# Flahser_4CH_555.net
KiCad netlist of a schematic drawn in Altium Designer
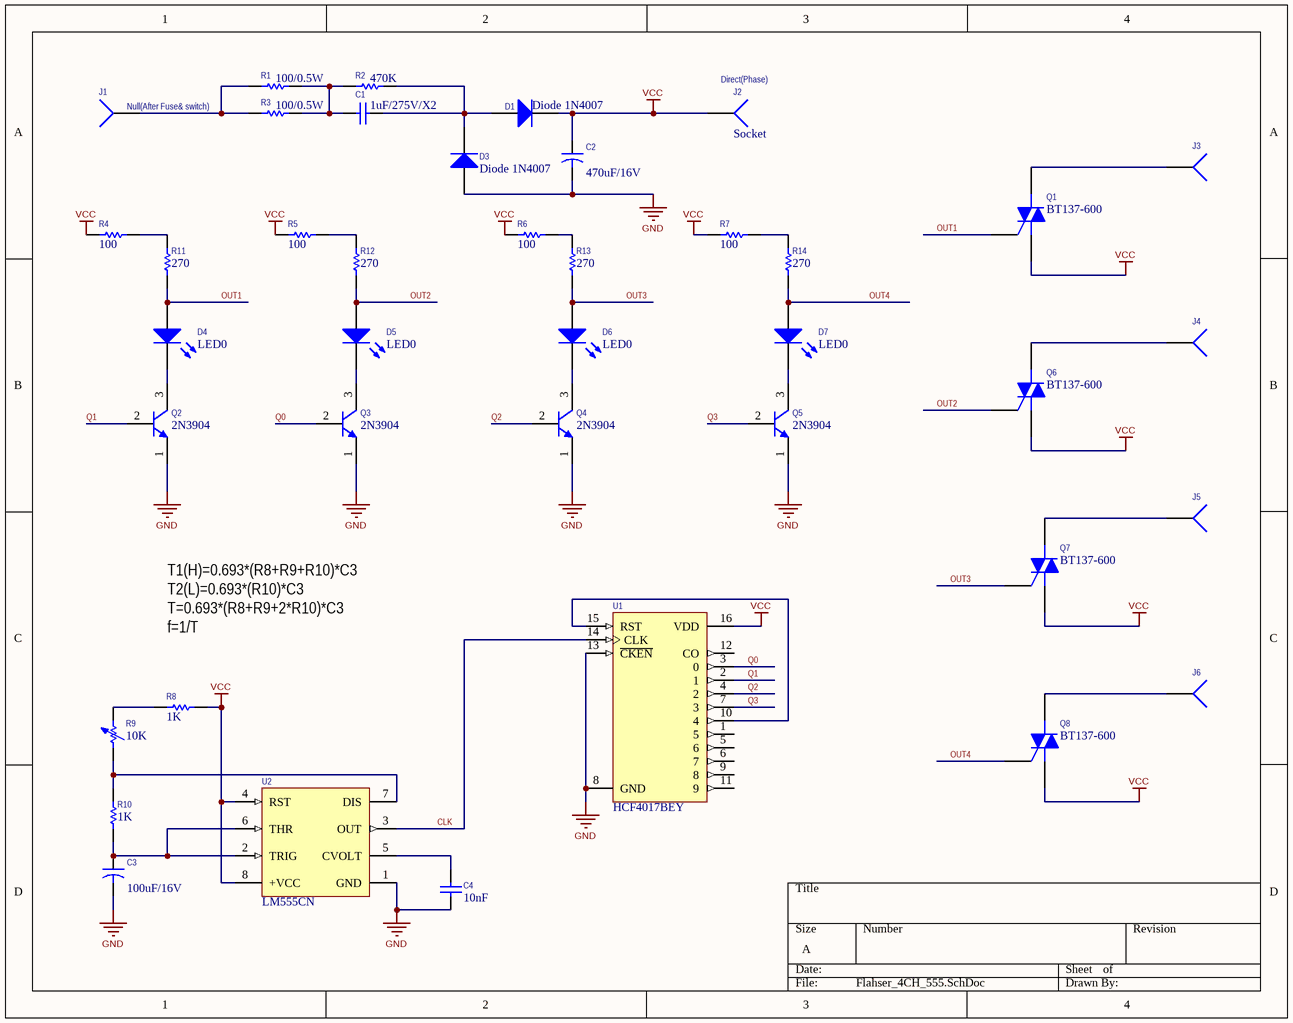
[diagram p0: Flahser_4CH_555.SchDoc]

(export (version "E")
  (design (tool "Eeschema 10.0.6"))
  (components
    (comp (ref "C1")
      (value "1uF/275V/X2")
      (footprint "Cap_polyester_275V_P22.5")
      (description "Capacitor")
      (fields (field (name "Comment") "Cap") (field (name "PUBLISHER") "Altium Limited"))
      (libsource (lib "Miscellaneous Devices") (part "Cap"))
    )
    (comp (ref "C2")
      (value "470uF/16V")
      (footprint "Cap electrolitic radial 8x12-3.5")
      (description "Capacitor")
      (fields (field (name "Comment") "Cap2") (field (name "PUBLISHER") "Altium Limited"))
      (libsource (lib "Miscellaneous Devices") (part "Cap2"))
    )
    (comp (ref "C3")
      (value "100uF/16V")
      (footprint "Cap electrolitic radial 5x11-2")
      (description "Capacitor")
      (fields (field (name "Comment") "Cap2") (field (name "PUBLISHER") "Altium Limited"))
      (libsource (lib "Miscellaneous Devices") (part "Cap2"))
    )
    (comp (ref "C4")
      (value "10nF")
      (footprint "CAP_MLCC_RAD_0.1")
      (description "Capacitor")
      (fields (field (name "Comment") "Cap") (field (name "PUBLISHER") "Altium Limited"))
      (libsource (lib "Miscellaneous Devices") (part "Cap"))
    )
    (comp (ref "D1")
      (value "Diode 1N4007")
      (footprint "DO-204AL")
      (description "1 Amp General Purpose Rectifier")
      (fields (field (name "PUBLISHER") "Altium Limited"))
      (libsource (lib "Miscellaneous Devices") (part "Diode 1N4007"))
    )
    (comp (ref "D3")
      (value "Diode 1N4007")
      (footprint "DO-204AL")
      (description "1 Amp General Purpose Rectifier")
      (fields (field (name "PUBLISHER") "Altium Limited"))
      (libsource (lib "Miscellaneous Devices") (part "Diode 1N4007"))
    )
    (comp (ref "D4")
      (value "LED0")
      (footprint "LED5MM_RED")
      (description "Typical INFRARED GaAs LED")
      (fields (field (name "PUBLISHER") "Altium Limited"))
      (libsource (lib "Miscellaneous Devices") (part "LED0"))
    )
    (comp (ref "D5")
      (value "LED0")
      (footprint "LED5MM_RED")
      (description "Typical INFRARED GaAs LED")
      (fields (field (name "PUBLISHER") "Altium Limited"))
      (libsource (lib "Miscellaneous Devices") (part "LED0"))
    )
    (comp (ref "D6")
      (value "LED0")
      (footprint "LED5MM_RED")
      (description "Typical INFRARED GaAs LED")
      (fields (field (name "PUBLISHER") "Altium Limited"))
      (libsource (lib "Miscellaneous Devices") (part "LED0"))
    )
    (comp (ref "D7")
      (value "LED0")
      (footprint "LED5MM_RED")
      (description "Typical INFRARED GaAs LED")
      (fields (field (name "PUBLISHER") "Altium Limited"))
      (libsource (lib "Miscellaneous Devices") (part "LED0"))
    )
    (comp (ref "J1")
      (value "Socket")
      (footprint "PIN1")
      (fields (field (name "PUBLISHER") "Altium Limited"))
      (libsource (lib "Miscellaneous Connectors") (part "Socket"))
    )
    (comp (ref "J2")
      (value "Socket")
      (footprint "PIN1")
      (fields (field (name "PUBLISHER") "Altium Limited"))
      (libsource (lib "Miscellaneous Connectors") (part "Socket"))
    )
    (comp (ref "J3")
      (value "Socket")
      (footprint "PIN1")
      (fields (field (name "PUBLISHER") "Altium Limited"))
      (libsource (lib "Miscellaneous Connectors") (part "Socket"))
    )
    (comp (ref "J4")
      (value "Socket")
      (footprint "PIN1")
      (fields (field (name "PUBLISHER") "Altium Limited"))
      (libsource (lib "Miscellaneous Connectors") (part "Socket"))
    )
    (comp (ref "J5")
      (value "Socket")
      (footprint "PIN1")
      (fields (field (name "PUBLISHER") "Altium Limited"))
      (libsource (lib "Miscellaneous Connectors") (part "Socket"))
    )
    (comp (ref "J6")
      (value "Socket")
      (footprint "PIN1")
      (fields (field (name "PUBLISHER") "Altium Limited"))
      (libsource (lib "Miscellaneous Connectors") (part "Socket"))
    )
    (comp (ref "Q1")
      (value "BT137-600")
      (footprint "TO-220 AB with heatsink ya25")
      (description "Silicon Bidirectional Triode Thyristor")
      (fields (field (name "PUBLISHER") "Altium Limited"))
      (libsource (lib "Miscellaneous Devices") (part "Triac"))
    )
    (comp (ref "Q2")
      (value "2N3904")
      (footprint "TO-92 CF")
      (description "NPN General Purpose Amplifier")
      (fields (field (name "PUBLISHER") "Altium Limited"))
      (libsource (lib "Miscellaneous Devices") (part "2N3904"))
    )
    (comp (ref "Q3")
      (value "2N3904")
      (footprint "TO-92 CF")
      (description "NPN General Purpose Amplifier")
      (fields (field (name "PUBLISHER") "Altium Limited"))
      (libsource (lib "Miscellaneous Devices") (part "2N3904"))
    )
    (comp (ref "Q4")
      (value "2N3904")
      (footprint "TO-92 CF")
      (description "NPN General Purpose Amplifier")
      (fields (field (name "PUBLISHER") "Altium Limited"))
      (libsource (lib "Miscellaneous Devices") (part "2N3904"))
    )
    (comp (ref "Q5")
      (value "2N3904")
      (footprint "TO-92 CF")
      (description "NPN General Purpose Amplifier")
      (fields (field (name "PUBLISHER") "Altium Limited"))
      (libsource (lib "Miscellaneous Devices") (part "2N3904"))
    )
    (comp (ref "Q6")
      (value "BT137-600")
      (footprint "TO-220 AB with heatsink ya25")
      (description "Silicon Bidirectional Triode Thyristor")
      (fields (field (name "PUBLISHER") "Altium Limited"))
      (libsource (lib "Miscellaneous Devices") (part "Triac"))
    )
    (comp (ref "Q7")
      (value "BT137-600")
      (footprint "TO-220 AB with heatsink ya25")
      (description "Silicon Bidirectional Triode Thyristor")
      (fields (field (name "PUBLISHER") "Altium Limited"))
      (libsource (lib "Miscellaneous Devices") (part "Triac"))
    )
    (comp (ref "Q8")
      (value "BT137-600")
      (footprint "TO-220 AB with heatsink ya25")
      (description "Silicon Bidirectional Triode Thyristor")
      (fields (field (name "PUBLISHER") "Altium Limited"))
      (libsource (lib "Miscellaneous Devices") (part "Triac"))
    )
    (comp (ref "R1")
      (value "100/0.5W")
      (footprint "Axial 0_5W 5_0mm")
      (description "Resistor")
      (fields (field (name "Comment") "Res1") (field (name "PUBLISHER") "Altium Limited"))
      (libsource (lib "Miscellaneous Devices") (part "Res1"))
    )
    (comp (ref "R2")
      (value "470K")
      (footprint "Axial 0_25 W, 0_4 IN LEAD PITCH")
      (description "Resistor")
      (fields (field (name "Comment") "Res1") (field (name "PUBLISHER") "Altium Limited"))
      (libsource (lib "Miscellaneous Devices") (part "Res1"))
    )
    (comp (ref "R3")
      (value "100/0.5W")
      (footprint "Axial 0_5W 5_0mm")
      (description "Resistor")
      (fields (field (name "Comment") "Res1") (field (name "PUBLISHER") "Altium Limited"))
      (libsource (lib "Miscellaneous Devices") (part "Res1"))
    )
    (comp (ref "R4")
      (value "100")
      (footprint "Axial 0_25 W, 0_4 IN LEAD PITCH")
      (description "Resistor")
      (fields (field (name "Comment") "Res1") (field (name "PUBLISHER") "Altium Limited"))
      (libsource (lib "Miscellaneous Devices") (part "Res1"))
    )
    (comp (ref "R5")
      (value "100")
      (footprint "Axial 0_25 W, 0_4 IN LEAD PITCH")
      (description "Resistor")
      (fields (field (name "Comment") "Res1") (field (name "PUBLISHER") "Altium Limited"))
      (libsource (lib "Miscellaneous Devices") (part "Res1"))
    )
    (comp (ref "R6")
      (value "100")
      (footprint "Axial 0_25 W, 0_4 IN LEAD PITCH")
      (description "Resistor")
      (fields (field (name "Comment") "Res1") (field (name "PUBLISHER") "Altium Limited"))
      (libsource (lib "Miscellaneous Devices") (part "Res1"))
    )
    (comp (ref "R7")
      (value "100")
      (footprint "Axial 0_25 W, 0_4 IN LEAD PITCH")
      (description "Resistor")
      (fields (field (name "Comment") "Res1") (field (name "PUBLISHER") "Altium Limited"))
      (libsource (lib "Miscellaneous Devices") (part "Res1"))
    )
    (comp (ref "R8")
      (value "1K")
      (footprint "Axial 0_25 W, 0_4 IN LEAD PITCH")
      (description "Resistor")
      (fields (field (name "Comment") "Res1") (field (name "PUBLISHER") "Altium Limited"))
      (libsource (lib "Miscellaneous Devices") (part "Res1"))
    )
    (comp (ref "R9")
      (value "10K")
      (footprint "AXIAL-0.4")
      (description "Variable Resistor")
      (fields (field (name "Comment") "Res Adj1") (field (name "PUBLISHER") "Altium Limited"))
      (libsource (lib "Miscellaneous Devices") (part "Res Adj1"))
    )
    (comp (ref "R10")
      (value "1K")
      (footprint "Axial 0_25 W, 0_4 IN LEAD PITCH")
      (description "Resistor")
      (fields (field (name "Comment") "Res1") (field (name "PUBLISHER") "Altium Limited"))
      (libsource (lib "Miscellaneous Devices") (part "Res1"))
    )
    (comp (ref "R11")
      (value "270")
      (footprint "Axial 0_25 W, 0_4 IN LEAD PITCH")
      (description "Resistor")
      (fields (field (name "Comment") "Res1") (field (name "PUBLISHER") "Altium Limited"))
      (libsource (lib "Miscellaneous Devices") (part "Res1"))
    )
    (comp (ref "R12")
      (value "270")
      (footprint "Axial 0_25 W, 0_4 IN LEAD PITCH")
      (description "Resistor")
      (fields (field (name "Comment") "Res1") (field (name "PUBLISHER") "Altium Limited"))
      (libsource (lib "Miscellaneous Devices") (part "Res1"))
    )
    (comp (ref "R13")
      (value "270")
      (footprint "Axial 0_25 W, 0_4 IN LEAD PITCH")
      (description "Resistor")
      (fields (field (name "Comment") "Res1") (field (name "PUBLISHER") "Altium Limited"))
      (libsource (lib "Miscellaneous Devices") (part "Res1"))
    )
    (comp (ref "R14")
      (value "270")
      (footprint "Axial 0_25 W, 0_4 IN LEAD PITCH")
      (description "Resistor")
      (fields (field (name "Comment") "Res1") (field (name "PUBLISHER") "Altium Limited"))
      (libsource (lib "Miscellaneous Devices") (part "Res1"))
    )
    (comp (ref "U1")
      (value "HCF4017BEY")
      (footprint "DIP16")
      (description "Decade Counter with 10 Decoded Outputs")
      (fields (field (name "PUBLISHER") "Altium Limited"))
      (libsource (lib "ST Logic Counter") (part "HCF4017BEY"))
    )
    (comp (ref "U2")
      (value "LM555CN")
      (footprint "8P3")
      (description "Timer, 8-pin MDIP")
      (fields
        (field (name "MANUFACTURER") "National Semiconductor")
        (field (name "PUBLISHER") "Altium Limited")
      )
      (libsource (lib "NSC Analog") (part "LM555CN"))
    )
  )
  (nets
    (net (code "1") (name "/CLK") (class "Default")
      (node (ref "U1") (pin "14") (pinfunction "CLK_14") (pintype "input"))
      (node (ref "U2") (pin "3") (pinfunction "OUT_3") (pintype "output"))
    )
    (net (code "2") (name "/OUT1") (class "Default")
      (node (ref "D4") (pin "1") (pinfunction "A_1") (pintype "passive"))
      (node (ref "Q1") (pin "3") (pinfunction "G_3") (pintype "passive"))
      (node (ref "R11") (pin "2") (pinfunction "2_2") (pintype "passive"))
    )
    (net (code "3") (name "/OUT2") (class "Default")
      (node (ref "D5") (pin "1") (pinfunction "A_1") (pintype "passive"))
      (node (ref "Q6") (pin "3") (pinfunction "G_3") (pintype "passive"))
      (node (ref "R12") (pin "2") (pinfunction "2_2") (pintype "passive"))
    )
    (net (code "4") (name "/OUT3") (class "Default")
      (node (ref "D6") (pin "1") (pinfunction "A_1") (pintype "passive"))
      (node (ref "Q7") (pin "3") (pinfunction "G_3") (pintype "passive"))
      (node (ref "R13") (pin "2") (pinfunction "2_2") (pintype "passive"))
    )
    (net (code "5") (name "/OUT4") (class "Default")
      (node (ref "D7") (pin "1") (pinfunction "A_1") (pintype "passive"))
      (node (ref "Q8") (pin "3") (pinfunction "G_3") (pintype "passive"))
      (node (ref "R14") (pin "2") (pinfunction "2_2") (pintype "passive"))
    )
    (net (code "6") (name "/Q0") (class "Default")
      (node (ref "Q3") (pin "2") (pinfunction "B_2") (pintype "passive"))
      (node (ref "U1") (pin "3") (pinfunction "0_3") (pintype "output"))
    )
    (net (code "7") (name "/Q1") (class "Default")
      (node (ref "Q2") (pin "2") (pinfunction "B_2") (pintype "passive"))
      (node (ref "U1") (pin "2") (pinfunction "1_2") (pintype "output"))
    )
    (net (code "8") (name "/Q2") (class "Default")
      (node (ref "Q4") (pin "2") (pinfunction "B_2") (pintype "passive"))
      (node (ref "U1") (pin "4") (pinfunction "2_4") (pintype "output"))
    )
    (net (code "9") (name "/Q3") (class "Default")
      (node (ref "Q5") (pin "2") (pinfunction "B_2") (pintype "passive"))
      (node (ref "U1") (pin "7") (pinfunction "3_7") (pintype "output"))
    )
    (net (code "10") (name "GND") (class "Default")
      (node (ref "C2") (pin "2") (pinfunction "2_2") (pintype "passive"))
      (node (ref "C3") (pin "2") (pinfunction "2_2") (pintype "passive"))
      (node (ref "C4") (pin "1") (pinfunction "1_1") (pintype "passive"))
      (node (ref "D3") (pin "1") (pinfunction "A_1") (pintype "passive"))
      (node (ref "Q2") (pin "1") (pinfunction "E_1") (pintype "passive"))
      (node (ref "Q3") (pin "1") (pinfunction "E_1") (pintype "passive"))
      (node (ref "Q4") (pin "1") (pinfunction "E_1") (pintype "passive"))
      (node (ref "Q5") (pin "1") (pinfunction "E_1") (pintype "passive"))
      (node (ref "U1") (pin "13") (pinfunction "~{CKEN}_13") (pintype "input"))
      (node (ref "U1") (pin "8") (pinfunction "GND_8") (pintype "power_in"))
      (node (ref "U2") (pin "1") (pinfunction "GND_1") (pintype "power_in"))
    )
    (net (code "11") (name "Net-(C1-Pad1)") (class "Default")
      (node (ref "C1") (pin "1") (pinfunction "1_1") (pintype "passive"))
      (node (ref "R1") (pin "2") (pinfunction "2_2") (pintype "passive"))
      (node (ref "R2") (pin "1") (pinfunction "1_1") (pintype "passive"))
      (node (ref "R3") (pin "2") (pinfunction "2_2") (pintype "passive"))
    )
    (net (code "12") (name "Net-(D1-A)") (class "Default")
      (node (ref "C1") (pin "2") (pinfunction "2_2") (pintype "passive"))
      (node (ref "D1") (pin "1") (pinfunction "A_1") (pintype "passive"))
      (node (ref "D3") (pin "2") (pinfunction "K_2") (pintype "passive"))
      (node (ref "R2") (pin "2") (pinfunction "2_2") (pintype "passive"))
    )
    (net (code "13") (name "Net-(D4-K)") (class "Default")
      (node (ref "D4") (pin "2") (pinfunction "K_2") (pintype "passive"))
      (node (ref "Q2") (pin "3") (pinfunction "C_3") (pintype "passive"))
    )
    (net (code "14") (name "Net-(D5-K)") (class "Default")
      (node (ref "D5") (pin "2") (pinfunction "K_2") (pintype "passive"))
      (node (ref "Q3") (pin "3") (pinfunction "C_3") (pintype "passive"))
    )
    (net (code "15") (name "Net-(D6-K)") (class "Default")
      (node (ref "D6") (pin "2") (pinfunction "K_2") (pintype "passive"))
      (node (ref "Q4") (pin "3") (pinfunction "C_3") (pintype "passive"))
    )
    (net (code "16") (name "Net-(D7-K)") (class "Default")
      (node (ref "D7") (pin "2") (pinfunction "K_2") (pintype "passive"))
      (node (ref "Q5") (pin "3") (pinfunction "C_3") (pintype "passive"))
    )
    (net (code "17") (name "Net-(J1-Pad1)") (class "Default")
      (node (ref "J1") (pin "1") (pinfunction "1_1") (pintype "passive"))
      (node (ref "R1") (pin "1") (pinfunction "1_1") (pintype "passive"))
      (node (ref "R3") (pin "1") (pinfunction "1_1") (pintype "passive"))
    )
    (net (code "18") (name "Net-(Q1-M2)") (class "Default")
      (node (ref "J3") (pin "1") (pinfunction "1_1") (pintype "passive"))
      (node (ref "Q1") (pin "2") (pinfunction "M2_2") (pintype "passive"))
    )
    (net (code "19") (name "Net-(Q6-M2)") (class "Default")
      (node (ref "J4") (pin "1") (pinfunction "1_1") (pintype "passive"))
      (node (ref "Q6") (pin "2") (pinfunction "M2_2") (pintype "passive"))
    )
    (net (code "20") (name "Net-(Q7-M2)") (class "Default")
      (node (ref "J5") (pin "1") (pinfunction "1_1") (pintype "passive"))
      (node (ref "Q7") (pin "2") (pinfunction "M2_2") (pintype "passive"))
    )
    (net (code "21") (name "Net-(Q8-M2)") (class "Default")
      (node (ref "J6") (pin "1") (pinfunction "1_1") (pintype "passive"))
      (node (ref "Q8") (pin "2") (pinfunction "M2_2") (pintype "passive"))
    )
    (net (code "22") (name "Net-(R8-Pad2)") (class "Default")
      (node (ref "R8") (pin "2") (pinfunction "2_2") (pintype "passive"))
      (node (ref "R9") (pin "2") (pinfunction "2_2") (pintype "passive"))
    )
    (net (code "23") (name "Net-(R11-Pad1)") (class "Default")
      (node (ref "R11") (pin "1") (pinfunction "1_1") (pintype "passive"))
      (node (ref "R4") (pin "1") (pinfunction "1_1") (pintype "passive"))
    )
    (net (code "24") (name "Net-(R12-Pad1)") (class "Default")
      (node (ref "R12") (pin "1") (pinfunction "1_1") (pintype "passive"))
      (node (ref "R5") (pin "1") (pinfunction "1_1") (pintype "passive"))
    )
    (net (code "25") (name "Net-(R13-Pad1)") (class "Default")
      (node (ref "R13") (pin "1") (pinfunction "1_1") (pintype "passive"))
      (node (ref "R6") (pin "1") (pinfunction "1_1") (pintype "passive"))
    )
    (net (code "26") (name "Net-(R14-Pad1)") (class "Default")
      (node (ref "R14") (pin "1") (pinfunction "1_1") (pintype "passive"))
      (node (ref "R7") (pin "1") (pinfunction "1_1") (pintype "passive"))
    )
    (net (code "27") (name "Net-(U1-4)") (class "Default")
      (node (ref "U1") (pin "10") (pinfunction "4_10") (pintype "output"))
      (node (ref "U1") (pin "15") (pinfunction "RST_15") (pintype "input"))
    )
    (net (code "28") (name "Net-(U2-CVOLT)") (class "Default")
      (node (ref "C4") (pin "2") (pinfunction "2_2") (pintype "passive"))
      (node (ref "U2") (pin "5") (pinfunction "CVOLT_5") (pintype "passive"))
    )
    (net (code "29") (name "Net-(U2-DIS)") (class "Default")
      (node (ref "R10") (pin "2") (pinfunction "2_2") (pintype "passive"))
      (node (ref "R9") (pin "1") (pinfunction "1_1") (pintype "passive"))
      (node (ref "U2") (pin "7") (pinfunction "DIS_7") (pintype "open_collector"))
    )
    (net (code "30") (name "Net-(U2-THR)") (class "Default")
      (node (ref "C3") (pin "1") (pinfunction "1_1") (pintype "passive"))
      (node (ref "R10") (pin "1") (pinfunction "1_1") (pintype "passive"))
      (node (ref "U2") (pin "2") (pinfunction "TRIG_2") (pintype "input"))
      (node (ref "U2") (pin "6") (pinfunction "THR_6") (pintype "input"))
    )
    (net (code "31") (name "VCC") (class "Default")
      (node (ref "C2") (pin "1") (pinfunction "1_1") (pintype "passive"))
      (node (ref "D1") (pin "2") (pinfunction "K_2") (pintype "passive"))
      (node (ref "J2") (pin "1") (pinfunction "1_1") (pintype "passive"))
      (node (ref "Q1") (pin "1") (pinfunction "M1_1") (pintype "passive"))
      (node (ref "Q6") (pin "1") (pinfunction "M1_1") (pintype "passive"))
      (node (ref "Q7") (pin "1") (pinfunction "M1_1") (pintype "passive"))
      (node (ref "Q8") (pin "1") (pinfunction "M1_1") (pintype "passive"))
      (node (ref "R4") (pin "2") (pinfunction "2_2") (pintype "passive"))
      (node (ref "R5") (pin "2") (pinfunction "2_2") (pintype "passive"))
      (node (ref "R6") (pin "2") (pinfunction "2_2") (pintype "passive"))
      (node (ref "R7") (pin "2") (pinfunction "2_2") (pintype "passive"))
      (node (ref "R8") (pin "1") (pinfunction "1_1") (pintype "passive"))
      (node (ref "U1") (pin "16") (pinfunction "VDD_16") (pintype "power_in"))
      (node (ref "U2") (pin "4") (pinfunction "RST_4") (pintype "input"))
      (node (ref "U2") (pin "8") (pinfunction "+VCC_8") (pintype "power_in"))
    )
    (net (code "32") (name "unconnected-(U1-5-Pad1)") (class "Default")
      (node (ref "U1") (pin "1") (pinfunction "5_1") (pintype "output"))
    )
    (net (code "33") (name "unconnected-(U1-6-Pad5)") (class "Default")
      (node (ref "U1") (pin "5") (pinfunction "6_5") (pintype "output"))
    )
    (net (code "34") (name "unconnected-(U1-7-Pad6)") (class "Default")
      (node (ref "U1") (pin "6") (pinfunction "7_6") (pintype "output"))
    )
    (net (code "35") (name "unconnected-(U1-8-Pad9)") (class "Default")
      (node (ref "U1") (pin "9") (pinfunction "8_9") (pintype "output"))
    )
    (net (code "36") (name "unconnected-(U1-9-Pad11)") (class "Default")
      (node (ref "U1") (pin "11") (pinfunction "9_11") (pintype "output"))
    )
    (net (code "37") (name "unconnected-(U1-CO-Pad12)") (class "Default")
      (node (ref "U1") (pin "12") (pinfunction "CO_12") (pintype "output"))
    )
  )
)
